# mcu.net
KiCad netlist of a schematic drawn in Altium Designer
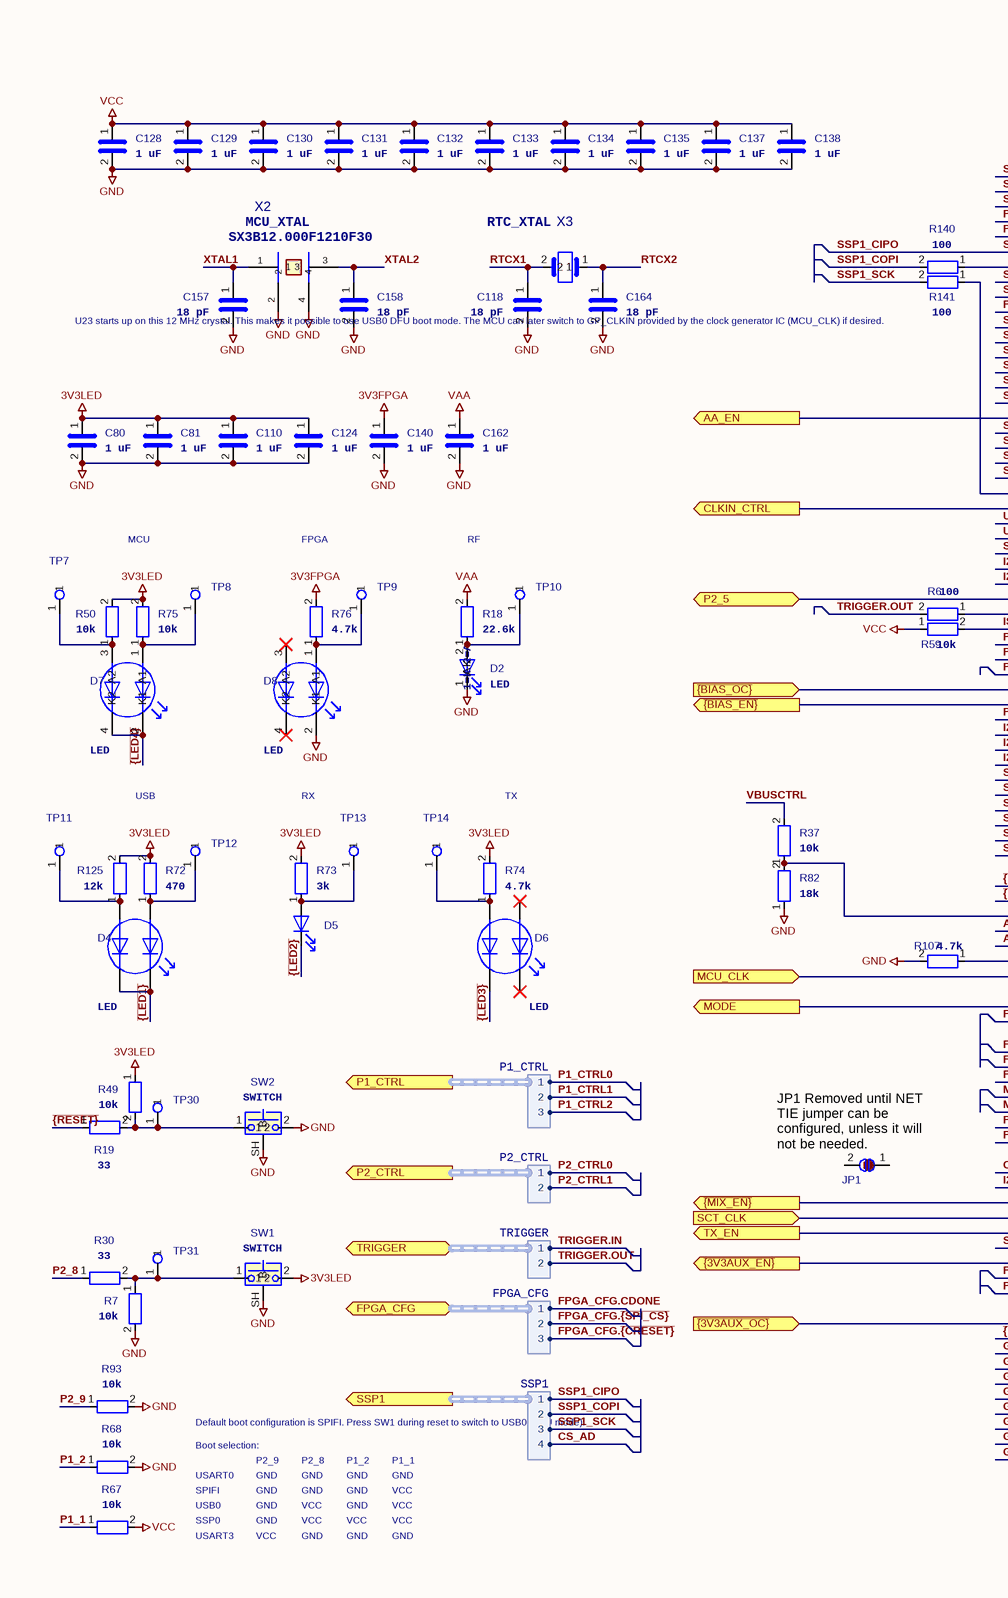
[diagram p0: mcu.SchDoc, left]
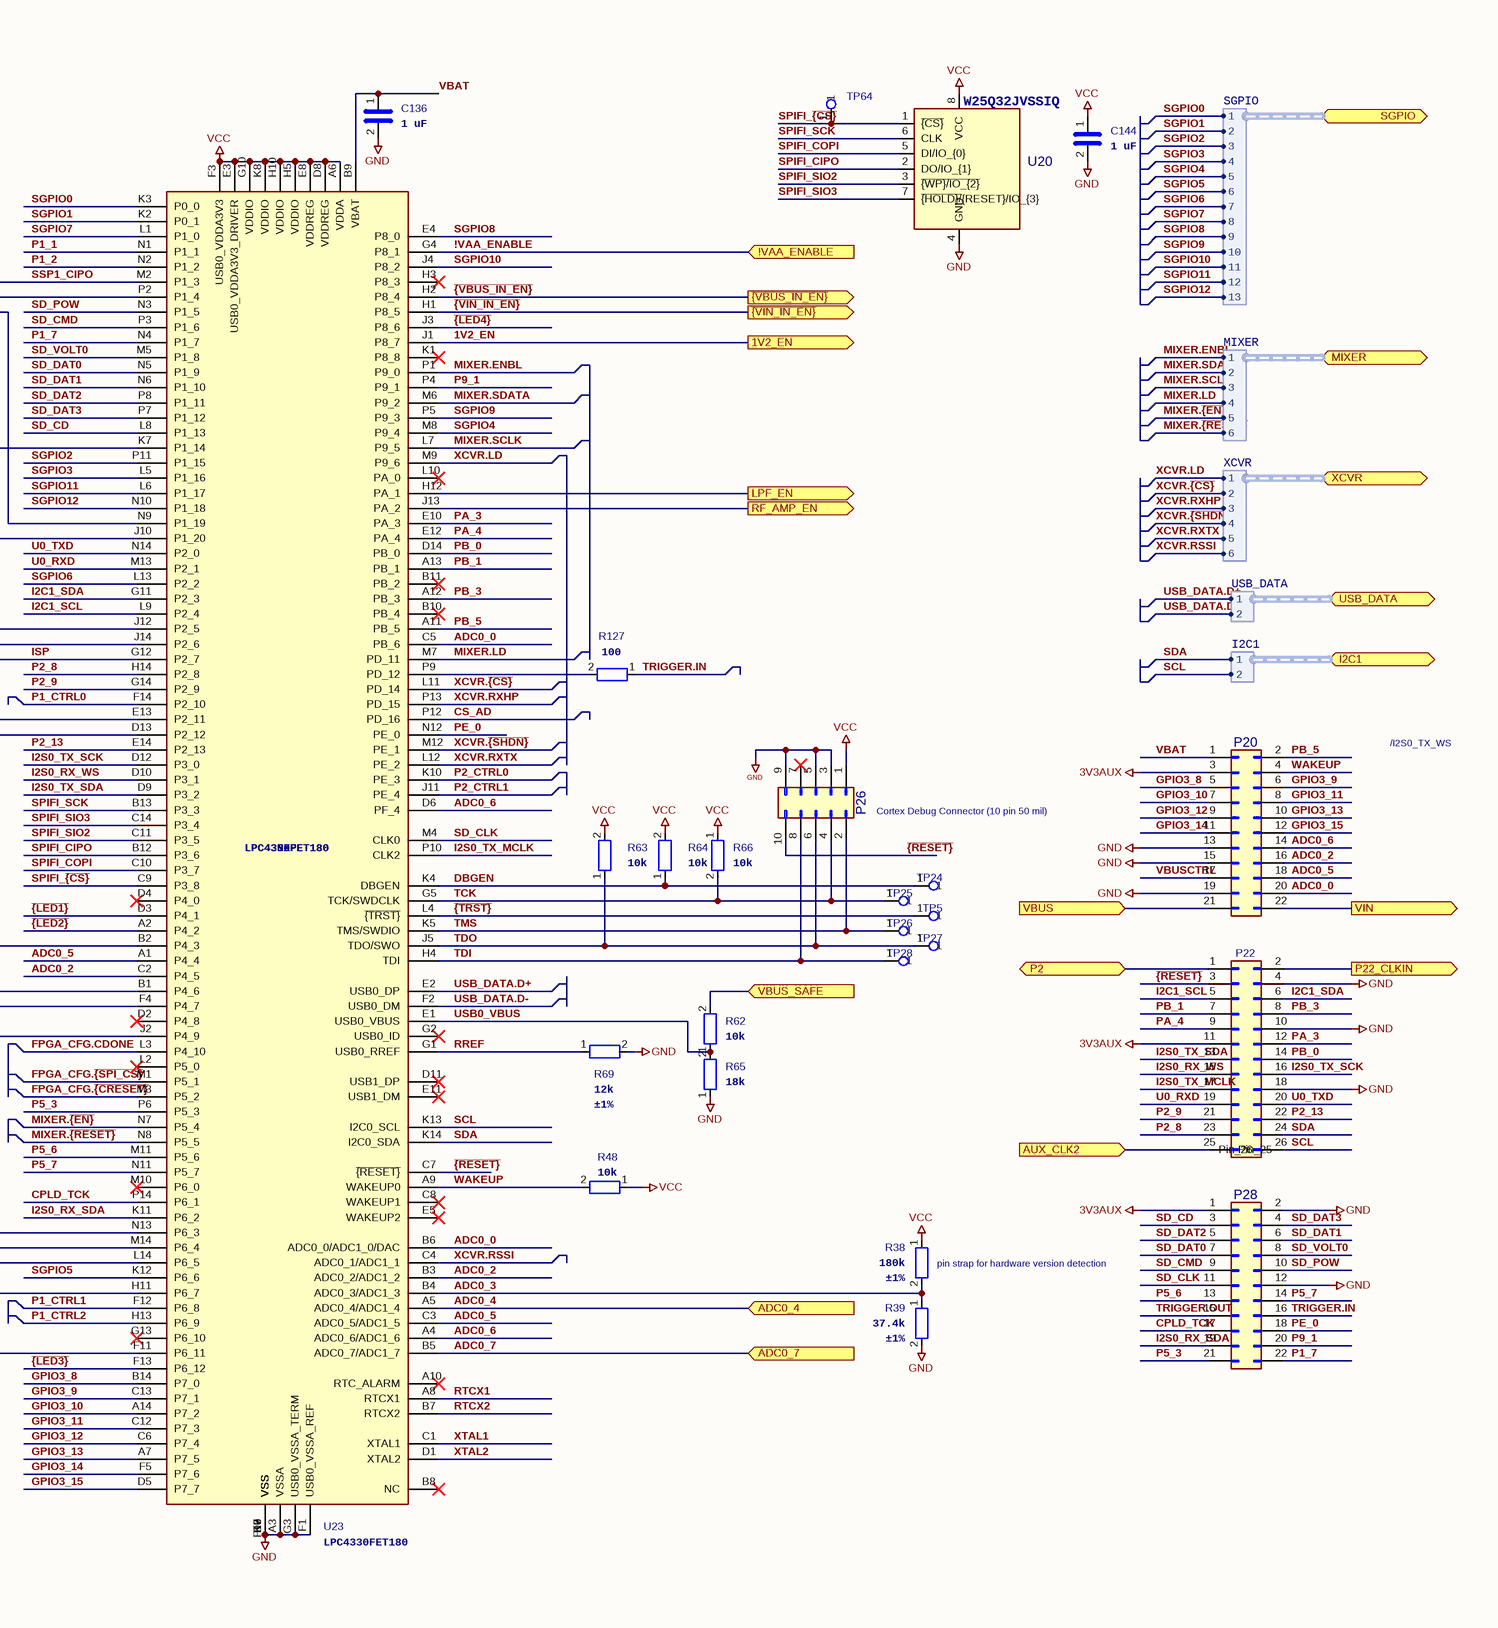
[diagram p1: mcu.SchDoc, right]

(export (version "E")
  (design (tool "Eeschema 10.0.6"))
  (components
    (comp (ref "C80")
      (value "1 uF")
      (footprint "C_0402_1005Metric")
      (fields (field (name "MANUFACTURER") "Samsung") (field (name "PART NUMBER") "CL05A105KA5NQNC"))
      (libsource (lib "Device") (part "C"))
    )
    (comp (ref "C81")
      (value "1 uF")
      (footprint "C_0402_1005Metric")
      (fields (field (name "MANUFACTURER") "Samsung") (field (name "PART NUMBER") "CL05A105KA5NQNC"))
      (libsource (lib "Device") (part "C"))
    )
    (comp (ref "C110")
      (value "1 uF")
      (footprint "C_0402_1005Metric")
      (fields (field (name "MANUFACTURER") "Samsung") (field (name "PART NUMBER") "CL05A105KA5NQNC"))
      (libsource (lib "Device") (part "C"))
    )
    (comp (ref "C118")
      (value "18 pF")
      (footprint "C_0402_1005Metric")
      (fields (field (name "MANUFACTURER") "Samsung") (field (name "PART NUMBER") "CL05C180JB5NNNC"))
      (libsource (lib "Device") (part "C"))
    )
    (comp (ref "C124")
      (value "1 uF")
      (footprint "C_0402_1005Metric")
      (fields (field (name "MANUFACTURER") "Samsung") (field (name "PART NUMBER") "CL05A105KA5NQNC"))
      (libsource (lib "Device") (part "C"))
    )
    (comp (ref "C128")
      (value "1 uF")
      (footprint "C_0402_1005Metric")
      (fields (field (name "MANUFACTURER") "Samsung") (field (name "PART NUMBER") "CL05A105KA5NQNC"))
      (libsource (lib "Device") (part "C"))
    )
    (comp (ref "C129")
      (value "1 uF")
      (footprint "C_0402_1005Metric")
      (fields (field (name "MANUFACTURER") "Samsung") (field (name "PART NUMBER") "CL05A105KA5NQNC"))
      (libsource (lib "Device") (part "C"))
    )
    (comp (ref "C130")
      (value "1 uF")
      (footprint "C_0402_1005Metric")
      (fields (field (name "MANUFACTURER") "Samsung") (field (name "PART NUMBER") "CL05A105KA5NQNC"))
      (libsource (lib "Device") (part "C"))
    )
    (comp (ref "C131")
      (value "1 uF")
      (footprint "C_0402_1005Metric")
      (fields (field (name "MANUFACTURER") "Samsung") (field (name "PART NUMBER") "CL05A105KA5NQNC"))
      (libsource (lib "Device") (part "C"))
    )
    (comp (ref "C132")
      (value "1 uF")
      (footprint "C_0402_1005Metric")
      (fields (field (name "MANUFACTURER") "Samsung") (field (name "PART NUMBER") "CL05A105KA5NQNC"))
      (libsource (lib "Device") (part "C"))
    )
    (comp (ref "C133")
      (value "1 uF")
      (footprint "C_0402_1005Metric")
      (fields (field (name "MANUFACTURER") "Samsung") (field (name "PART NUMBER") "CL05A105KA5NQNC"))
      (libsource (lib "Device") (part "C"))
    )
    (comp (ref "C134")
      (value "1 uF")
      (footprint "C_0402_1005Metric")
      (fields (field (name "MANUFACTURER") "Samsung") (field (name "PART NUMBER") "CL05A105KA5NQNC"))
      (libsource (lib "Device") (part "C"))
    )
    (comp (ref "C135")
      (value "1 uF")
      (footprint "C_0402_1005Metric")
      (fields (field (name "MANUFACTURER") "Samsung") (field (name "PART NUMBER") "CL05A105KA5NQNC"))
      (libsource (lib "Device") (part "C"))
    )
    (comp (ref "C136")
      (value "1 uF")
      (footprint "C_0402_1005Metric")
      (fields (field (name "MANUFACTURER") "Samsung") (field (name "PART NUMBER") "CL05A105KA5NQNC"))
      (libsource (lib "Device") (part "C"))
    )
    (comp (ref "C137")
      (value "1 uF")
      (footprint "C_0402_1005Metric")
      (fields (field (name "MANUFACTURER") "Samsung") (field (name "PART NUMBER") "CL05A105KA5NQNC"))
      (libsource (lib "Device") (part "C"))
    )
    (comp (ref "C138")
      (value "1 uF")
      (footprint "C_0402_1005Metric")
      (fields (field (name "MANUFACTURER") "Samsung") (field (name "PART NUMBER") "CL05A105KA5NQNC"))
      (libsource (lib "Device") (part "C"))
    )
    (comp (ref "C140")
      (value "1 uF")
      (footprint "C_0402_1005Metric")
      (fields (field (name "MANUFACTURER") "Samsung") (field (name "PART NUMBER") "CL05A105KA5NQNC"))
      (libsource (lib "Device") (part "C"))
    )
    (comp (ref "C144")
      (value "1 uF")
      (footprint "C_0402_1005Metric")
      (fields (field (name "MANUFACTURER") "Samsung") (field (name "PART NUMBER") "CL05A105KA5NQNC"))
      (libsource (lib "Device") (part "C"))
    )
    (comp (ref "C157")
      (value "18 pF")
      (footprint "C_0402_1005Metric")
      (fields (field (name "MANUFACTURER") "Samsung") (field (name "PART NUMBER") "CL05C180JB5NNNC"))
      (libsource (lib "Device") (part "C"))
    )
    (comp (ref "C158")
      (value "18 pF")
      (footprint "C_0402_1005Metric")
      (fields (field (name "MANUFACTURER") "Samsung") (field (name "PART NUMBER") "CL05C180JB5NNNC"))
      (libsource (lib "Device") (part "C"))
    )
    (comp (ref "C162")
      (value "1 uF")
      (footprint "C_0402_1005Metric")
      (fields (field (name "MANUFACTURER") "Samsung") (field (name "PART NUMBER") "CL05A105KA5NQNC"))
      (libsource (lib "Device") (part "C"))
    )
    (comp (ref "C164")
      (value "18 pF")
      (footprint "C_0402_1005Metric")
      (fields (field (name "MANUFACTURER") "Samsung") (field (name "PART NUMBER") "CL05C180JB5NNNC"))
      (libsource (lib "Device") (part "C"))
    )
    (comp (ref "D2")
      (value "LED")
      (footprint "LED_Single_Xinglight_XL-3210_Horizontal")
      (fields
        (field (name "MANUFACTURER") "Xinglight")
        (field (name "PART NUMBER") "XL-3210UGC")
        (field (name "SIM.PINS") "1=K 2=A")
      )
      (libsource (lib "") (part "LED_1"))
    )
    (comp (ref "D4")
      (value "LED")
      (footprint "LED_Dual_Xinglight_XL-3210_Horizontal")
      (fields (field (name "MANUFACTURER") "Xinglight") (field (name "PART NUMBER") "XL-3210SURSYGC"))
      (libsource (lib "Device") (part "LED_Dual_AKAK"))
    )
    (comp (ref "D5")
      (value "LED")
      (footprint "LED_Single_Xinglight_XL-3210_Horizontal")
      (fields (field (name "MANUFACTURER") "Xinglight") (field (name "PART NUMBER") "XL-3210UOC"))
      (libsource (lib "Device") (part "LED"))
    )
    (comp (ref "D6")
      (value "LED")
      (footprint "LED_Dual_Xinglight_XL-3210_Horizontal")
      (fields (field (name "MANUFACTURER") "Xinglight") (field (name "PART NUMBER") "XL-3210SURUBC"))
      (libsource (lib "Device") (part "LED_Dual_AKAK"))
    )
    (comp (ref "D7")
      (value "LED")
      (footprint "LED_Dual_Xinglight_XL-3210_Horizontal")
      (fields (field (name "MANUFACTURER") "Xinglight") (field (name "PART NUMBER") "XL-3210SURUBC"))
      (libsource (lib "") (part "LED_Dual_AKAK_1"))
    )
    (comp (ref "D8")
      (value "LED")
      (footprint "LED_Dual_Xinglight_XL-3210_Horizontal")
      (fields (field (name "MANUFACTURER") "Xinglight") (field (name "PART NUMBER") "XL-3210SURUBC"))
      (libsource (lib "") (part "LED_Dual_AKAK_1"))
    )
    (comp (ref "JP1")
      (value "SolderJumper_2_Bridged")
      (footprint "SolderJumper-2_P1.3mm_Bridged_RoundedPad1.0x1.5mm")
      (libsource (lib "Jumper") (part "SolderJumper_2_Bridged"))
    )
    (comp (ref "P20")
      (value "HEADER_2x11")
      (footprint "PinSocket_2x11_P2.54mm_Vertical_Flipped")
      (fields (field (name "MANUFACTURER") "Sullins") (field (name "PART NUMBER") "PPPC112LFBN-RC"))
      (libsource (lib "Connector_Generic") (part "Conn_02x11_Odd_Even"))
    )
    (comp (ref "P22")
      (value "HEADER_2x13")
      (footprint "PinSocket_2x13_P2.54mm_Vertical_Flipped")
      (fields (field (name "MANUFACTURER") "Sullins") (field (name "PART NUMBER") "PPPC132LFBN-RC"))
      (libsource (lib "Connector_Generic") (part "Conn_02x13_Odd_Even"))
    )
    (comp (ref "P26")
      (value "LPC_JTAG")
      (footprint "PinHeader_2x05_P1.27mm_Vertical")
      (fields (field (name "MANUFACTURER") "Sullins") (field (name "PART NUMBER") "GRPB052VWVN-RC"))
      (libsource (lib "Connector_Generic") (part "Conn_02x05_Odd_Even"))
    )
    (comp (ref "P28")
      (value "HEADER_2x11")
      (footprint "PinSocket_2x11_P2.54mm_Vertical_Flipped")
      (fields (field (name "MANUFACTURER") "Sullins") (field (name "PART NUMBER") "PPPC112LFBN-RC"))
      (libsource (lib "Connector_Generic") (part "Conn_02x11_Odd_Even"))
    )
    (comp (ref "R6")
      (value "100")
      (footprint "R_0201_0603Metric")
      (fields (field (name "MANUFACTURER") "Yageo") (field (name "PART NUMBER") "RC0201JR-07100RL"))
      (libsource (lib "") (part "R_2"))
    )
    (comp (ref "R7")
      (value "10k")
      (footprint "R_0402_1005Metric")
      (fields (field (name "MANUFACTURER") "Yageo") (field (name "PART NUMBER") "RC0402JR-0710KL"))
      (libsource (lib "") (part "R_3"))
    )
    (comp (ref "R18")
      (value "22.6k")
      (footprint "R_0201_0603Metric")
      (fields (field (name "MANUFACTURER") "Yageo") (field (name "PART NUMBER") "RC0201FR-0722K6L"))
      (libsource (lib "") (part "R_1"))
    )
    (comp (ref "R19")
      (value "33")
      (footprint "R_0201_0603Metric")
      (fields (field (name "MANUFACTURER") "Yageo") (field (name "PART NUMBER") "RC0201JR-0733RL"))
      (libsource (lib "") (part "R_1"))
    )
    (comp (ref "R30")
      (value "33")
      (footprint "R_0201_0603Metric")
      (fields (field (name "MANUFACTURER") "Yageo") (field (name "PART NUMBER") "RC0201JR-0733RL"))
      (libsource (lib "Device") (part "R"))
    )
    (comp (ref "R37")
      (value "10k")
      (footprint "R_0402_1005Metric")
      (fields (field (name "MANUFACTURER") "Yageo") (field (name "PART NUMBER") "RC0402JR-0710KL"))
      (libsource (lib "") (part "R_1"))
    )
    (comp (ref "R38")
      (value "180k")
      (footprint "R_0402_1005Metric")
      (fields
        (field (name "MANUFACTURER") "Yageo")
        (field (name "PART NUMBER") "RC0402FR-07180KL")
        (field (name "TOLERANCE") "±1%")
      )
      (libsource (lib "") (part "R_2"))
    )
    (comp (ref "R39")
      (value "37.4k")
      (footprint "R_0402_1005Metric")
      (fields
        (field (name "MANUFACTURER") "Yageo")
        (field (name "PART NUMBER") "RC0402FR-0737K4L")
        (field (name "TOLERANCE") "±1%")
      )
      (libsource (lib "") (part "R_2"))
    )
    (comp (ref "R48")
      (value "10k")
      (footprint "R_0402_1005Metric")
      (fields (field (name "MANUFACTURER") "Yageo") (field (name "PART NUMBER") "RC0402JR-0710KL"))
      (libsource (lib "") (part "R_3"))
    )
    (comp (ref "R49")
      (value "10k")
      (footprint "R_0402_1005Metric")
      (fields (field (name "MANUFACTURER") "Yageo") (field (name "PART NUMBER") "RC0402JR-0710KL"))
      (libsource (lib "") (part "R_2"))
    )
    (comp (ref "R50")
      (value "10k")
      (footprint "R_0402_1005Metric")
      (fields (field (name "MANUFACTURER") "Yageo") (field (name "PART NUMBER") "RC0402JR-0710KL"))
      (libsource (lib "") (part "R_1"))
    )
    (comp (ref "R59")
      (value "10k")
      (footprint "R_0402_1005Metric")
      (fields (field (name "MANUFACTURER") "Yageo") (field (name "PART NUMBER") "RC0402JR-0710KL"))
      (libsource (lib "Device") (part "R"))
    )
    (comp (ref "R62")
      (value "10k")
      (footprint "R_0402_1005Metric")
      (fields (field (name "MANUFACTURER") "Yageo") (field (name "PART NUMBER") "RC0402JR-0710KL"))
      (libsource (lib "") (part "R_1"))
    )
    (comp (ref "R63")
      (value "10k")
      (footprint "R_0402_1005Metric")
      (fields (field (name "MANUFACTURER") "Yageo") (field (name "PART NUMBER") "RC0402JR-0710KL"))
      (libsource (lib "") (part "R_1"))
    )
    (comp (ref "R64")
      (value "10k")
      (footprint "R_0402_1005Metric")
      (fields (field (name "MANUFACTURER") "Yageo") (field (name "PART NUMBER") "RC0402JR-0710KL"))
      (libsource (lib "") (part "R_1"))
    )
    (comp (ref "R65")
      (value "18k")
      (footprint "R_0402_1005Metric")
      (fields (field (name "MANUFACTURER") "Yageo") (field (name "PART NUMBER") "RC0402JR-0718KL"))
      (libsource (lib "") (part "R_1"))
    )
    (comp (ref "R66")
      (value "10k")
      (footprint "R_0402_1005Metric")
      (fields (field (name "MANUFACTURER") "Yageo") (field (name "PART NUMBER") "RC0402JR-0710KL"))
      (libsource (lib "") (part "R_2"))
    )
    (comp (ref "R67")
      (value "10k")
      (footprint "R_0402_1005Metric")
      (fields (field (name "MANUFACTURER") "Yageo") (field (name "PART NUMBER") "RC0402JR-0710KL"))
      (libsource (lib "Device") (part "R"))
    )
    (comp (ref "R68")
      (value "10k")
      (footprint "R_0402_1005Metric")
      (fields (field (name "MANUFACTURER") "Yageo") (field (name "PART NUMBER") "RC0402JR-0710KL"))
      (libsource (lib "") (part "R_1"))
    )
    (comp (ref "R69")
      (value "12k")
      (footprint "R_0201_0603Metric")
      (fields
        (field (name "MANUFACTURER") "Yageo")
        (field (name "PART NUMBER") "RC0201FR-0712KL")
        (field (name "TOLERANCE") "±1%")
      )
      (libsource (lib "") (part "R_1"))
    )
    (comp (ref "R72")
      (value "470")
      (footprint "R_0201_0603Metric")
      (fields (field (name "MANUFACTURER") "Yageo") (field (name "PART NUMBER") "RC0201JR-07470RL"))
      (libsource (lib "") (part "R_1"))
    )
    (comp (ref "R73")
      (value "3k")
      (footprint "R_0402_1005Metric")
      (fields (field (name "MANUFACTURER") "Yageo") (field (name "PART NUMBER") "RC0402JR-073KL"))
      (libsource (lib "") (part "R_1"))
    )
    (comp (ref "R74")
      (value "4.7k")
      (footprint "R_0201_0603Metric")
      (fields (field (name "MANUFACTURER") "Yageo") (field (name "PART NUMBER") "RC0201FR-074K7L"))
      (libsource (lib "") (part "R_1"))
    )
    (comp (ref "R75")
      (value "10k")
      (footprint "R_0402_1005Metric")
      (fields (field (name "MANUFACTURER") "Yageo") (field (name "PART NUMBER") "RC0402JR-0710KL"))
      (libsource (lib "") (part "R_1"))
    )
    (comp (ref "R76")
      (value "4.7k")
      (footprint "R_0201_0603Metric")
      (fields (field (name "MANUFACTURER") "Yageo") (field (name "PART NUMBER") "RC0201FR-074K7L"))
      (libsource (lib "") (part "R_1"))
    )
    (comp (ref "R82")
      (value "18k")
      (footprint "R_0402_1005Metric")
      (fields (field (name "MANUFACTURER") "Yageo") (field (name "PART NUMBER") "RC0402JR-0718KL"))
      (libsource (lib "") (part "R_1"))
    )
    (comp (ref "R93")
      (value "10k")
      (footprint "R_0402_1005Metric")
      (fields (field (name "MANUFACTURER") "Yageo") (field (name "PART NUMBER") "RC0402JR-0710KL"))
      (libsource (lib "") (part "R_1"))
    )
    (comp (ref "R107")
      (value "4.7k")
      (footprint "R_0201_0603Metric")
      (fields (field (name "MANUFACTURER") "Yageo") (field (name "PART NUMBER") "RC0201FR-074K7L"))
      (libsource (lib "") (part "R_2"))
    )
    (comp (ref "R125")
      (value "12k")
      (footprint "R_0201_0603Metric")
      (fields (field (name "MANUFACTURER") "Yageo") (field (name "PART NUMBER") "RC0201FR-0712KL"))
      (libsource (lib "") (part "R_1"))
    )
    (comp (ref "R127")
      (value "100")
      (footprint "R_0201_0603Metric")
      (fields (field (name "MANUFACTURER") "Yageo") (field (name "PART NUMBER") "RC0201JR-07100RL"))
      (libsource (lib "") (part "R_2"))
    )
    (comp (ref "R140")
      (value "100")
      (footprint "R_0201_0603Metric")
      (fields (field (name "MANUFACTURER") "Yageo") (field (name "PART NUMBER") "RC0201JR-07100RL"))
      (libsource (lib "") (part "R_2"))
    )
    (comp (ref "R141")
      (value "100")
      (footprint "R_0201_0603Metric")
      (fields (field (name "MANUFACTURER") "Yageo") (field (name "PART NUMBER") "RC0201JR-07100RL"))
      (libsource (lib "") (part "R_2"))
    )
    (comp (ref "SW1")
      (value "SWITCH")
      (footprint "SW_Tactile_SPST_Angled_PTS645Vx58-2LFS")
      (fields (field (name "MANUFACTURER") "TE Connectivity") (field (name "PART NUMBER") "FSMRA3JH"))
      (libsource (lib "Switch") (part "SW_Push_Shielded"))
    )
    (comp (ref "SW2")
      (value "SWITCH")
      (footprint "SW_Tactile_SPST_Angled_PTS645Vx58-2LFS")
      (fields (field (name "MANUFACTURER") "TE Connectivity") (field (name "PART NUMBER") "FSMRA3JH"))
      (libsource (lib "Switch") (part "SW_Push_Shielded"))
    )
    (comp (ref "TP5")
      (value "TestPoint")
      (footprint "TestPoint_Pad_D1.0mm")
      (libsource (lib "Connector") (part "TestPoint"))
    )
    (comp (ref "TP7")
      (value "TestPoint")
      (footprint "TestPoint_Pad_D1.0mm")
      (libsource (lib "Connector") (part "TestPoint"))
    )
    (comp (ref "TP8")
      (value "TestPoint")
      (footprint "TestPoint_Pad_D1.0mm")
      (libsource (lib "Connector") (part "TestPoint"))
    )
    (comp (ref "TP9")
      (value "TestPoint")
      (footprint "TestPoint_Pad_D1.0mm")
      (libsource (lib "Connector") (part "TestPoint"))
    )
    (comp (ref "TP10")
      (value "TestPoint")
      (footprint "TestPoint_Pad_D1.0mm")
      (libsource (lib "Connector") (part "TestPoint"))
    )
    (comp (ref "TP11")
      (value "TestPoint")
      (footprint "TestPoint_Pad_D1.0mm")
      (libsource (lib "Connector") (part "TestPoint"))
    )
    (comp (ref "TP12")
      (value "TestPoint")
      (footprint "TestPoint_Pad_D1.0mm")
      (libsource (lib "Connector") (part "TestPoint"))
    )
    (comp (ref "TP13")
      (value "TestPoint")
      (footprint "TestPoint_Pad_D1.0mm")
      (libsource (lib "Connector") (part "TestPoint"))
    )
    (comp (ref "TP14")
      (value "TestPoint")
      (footprint "TestPoint_Pad_D1.0mm")
      (libsource (lib "Connector") (part "TestPoint"))
    )
    (comp (ref "TP24")
      (value "TestPoint")
      (footprint "TestPoint_Pad_D1.0mm")
      (libsource (lib "Connector") (part "TestPoint"))
    )
    (comp (ref "TP25")
      (value "TestPoint")
      (footprint "TestPoint_Pad_D1.0mm")
      (libsource (lib "Connector") (part "TestPoint"))
    )
    (comp (ref "TP26")
      (value "TestPoint")
      (footprint "TestPoint_Pad_D1.0mm")
      (libsource (lib "Connector") (part "TestPoint"))
    )
    (comp (ref "TP27")
      (value "TestPoint")
      (footprint "TestPoint_Pad_D1.0mm")
      (libsource (lib "Connector") (part "TestPoint"))
    )
    (comp (ref "TP28")
      (value "TestPoint")
      (footprint "TestPoint_Pad_D1.0mm")
      (libsource (lib "Connector") (part "TestPoint"))
    )
    (comp (ref "TP30")
      (value "TestPoint")
      (footprint "TestPoint_Pad_D1.0mm")
      (libsource (lib "Connector") (part "TestPoint"))
    )
    (comp (ref "TP31")
      (value "TestPoint")
      (footprint "TestPoint_Pad_D1.0mm")
      (libsource (lib "Connector") (part "TestPoint"))
    )
    (comp (ref "TP64")
      (value "TestPoint")
      (footprint "TestPoint_Pad_D1.0mm")
      (libsource (lib "Connector") (part "TestPoint"))
    )
    (comp (ref "U20")
      (value "W25Q32")
      (footprint "SOIC-8_5.3x5.3mm_P1.27mm")
      (fields (field (name "MANUFACTURER") "Winbond") (field (name "PART NUMBER") "W25Q32JVSSIQ"))
      (libsource (lib "Memory_Flash") (part "W25Q32JVSS"))
    )
    (comp (ref "U23")
      (value "LPC4330FET180")
      (footprint "TFBGA-180_12x12mm_Layout14x14_P0.8mm")
      (fields
        (field (name "MANUFACTURER") "NXP")
        (field (name "PART NUMBER") "LPC4330FET180")
        (field (name "SUBSTITUTION") "LPC4350FET180")
      )
      (libsource (lib "praline") (part "LPC43xxFET180"))
    )
    (comp (ref "X2")
      (value "MCU_XTAL")
      (footprint "Crystal_SMD_3225-4Pin_3.2x2.5mm")
      (fields
        (field (name "MANUFACTURER") "Shenzhen SCTF Electronics")
        (field (name "PART NUMBER") "SX3B12.000F1210F30")
      )
      (libsource (lib "hackrf") (part "GSG-XTAL4PIN"))
    )
    (comp (ref "X3")
      (value "RTC_XTAL")
      (footprint "Crystal_SMD_3215-2Pin_3.2x1.5mm")
      (fields (field (name "MANUFACTURER") "YXC") (field (name "PART NUMBER") "XKXGI-SUA-32.768K"))
      (libsource (lib "Device") (part "Crystal"))
    )
  )
  (nets
    (net (code "11") (name "/!VAA_ENABLE") (class "Default")
      (node (ref "U23") (pin "G4") (pinfunction "P8_1_G4") (pintype "passive"))
    )
    (net (code "12") (name "/1V2_EN") (class "Default")
      (node (ref "U23") (pin "J1") (pinfunction "P8_7_J1") (pintype "passive"))
    )
    (net (code "13") (name "/AA_EN") (class "Default")
      (node (ref "U23") (pin "K7") (pinfunction "P1_14_K7") (pintype "passive"))
    )
    (net (code "14") (name "/ADC0_0") (class "Default")
      (node (ref "P20") (pin "20") (pinfunction "Pin_20_20") (pintype "passive"))
      (node (ref "U23") (pin "B6") (pinfunction "ADC0_0/ADC1_0/DAC_B6") (pintype "passive"))
      (node (ref "U23") (pin "C5") (pinfunction "PB_6_C5") (pintype "passive"))
    )
    (net (code "15") (name "/ADC0_2") (class "Default")
      (node (ref "P20") (pin "16") (pinfunction "Pin_16_16") (pintype "passive"))
      (node (ref "U23") (pin "B3") (pinfunction "ADC0_2/ADC1_2_B3") (pintype "passive"))
      (node (ref "U23") (pin "C2") (pinfunction "P4_5_C2") (pintype "passive"))
    )
    (net (code "16") (name "/ADC0_3") (class "Default")
      (node (ref "R38") (pin "2") (pinfunction "2_2") (pintype "passive"))
      (node (ref "R39") (pin "1") (pinfunction "1_1") (pintype "passive"))
      (node (ref "U23") (pin "B4") (pinfunction "ADC0_3/ADC1_3_B4") (pintype "passive"))
    )
    (net (code "17") (name "/ADC0_4") (class "Default")
      (node (ref "U23") (pin "A5") (pinfunction "ADC0_4/ADC1_4_A5") (pintype "passive"))
    )
    (net (code "18") (name "/ADC0_5") (class "Default")
      (node (ref "P20") (pin "18") (pinfunction "Pin_18_18") (pintype "passive"))
      (node (ref "U23") (pin "A1") (pinfunction "P4_4_A1") (pintype "passive"))
      (node (ref "U23") (pin "C3") (pinfunction "ADC0_5/ADC1_5_C3") (pintype "passive"))
    )
    (net (code "19") (name "/ADC0_6") (class "Default")
      (node (ref "P20") (pin "14") (pinfunction "Pin_14_14") (pintype "passive"))
      (node (ref "U23") (pin "A4") (pinfunction "ADC0_6/ADC1_6_A4") (pintype "passive"))
      (node (ref "U23") (pin "D6") (pinfunction "PF_4_D6") (pintype "passive"))
    )
    (net (code "20") (name "/ADC0_7") (class "Default")
      (node (ref "U23") (pin "B5") (pinfunction "ADC0_7/ADC1_7_B5") (pintype "passive"))
    )
    (net (code "21") (name "/AUX_CLK2") (class "Default")
      (node (ref "P22") (pin "25") (pinfunction "Pin_25_25") (pintype "passive"))
    )
    (net (code "22") (name "/CLKIN_CTRL") (class "Default")
      (node (ref "U23") (pin "J10") (pinfunction "P1_20_J10") (pintype "passive"))
    )
    (net (code "23") (name "/CPLD_TCK") (class "Default")
      (node (ref "P28") (pin "17") (pinfunction "Pin_17_17") (pintype "passive"))
      (node (ref "U23") (pin "P14") (pinfunction "P6_1_P14") (pintype "passive"))
    )
    (net (code "24") (name "/CS_AD") (class "Default")
      (node (ref "U23") (pin "P12") (pinfunction "PD_16_P12") (pintype "passive"))
    )
    (net (code "25") (name "/DBGEN") (class "Default")
      (node (ref "R64") (pin "1") (pinfunction "1_1") (pintype "passive"))
      (node (ref "TP24") (pin "1") (pinfunction "1_1") (pintype "passive"))
      (node (ref "U23") (pin "K4") (pinfunction "DBGEN_K4") (pintype "passive"))
    )
    (net (code "26") (name "/FPGA_CFG.CDONE") (class "Default")
      (node (ref "U23") (pin "L3") (pinfunction "P4_10_L3") (pintype "passive"))
    )
    (net (code "27") (name "/FPGA_CFG.~{{CRESET}}") (class "Default")
      (node (ref "U23") (pin "M3") (pinfunction "P5_2_M3") (pintype "passive"))
    )
    (net (code "28") (name "/FPGA_CFG.~{{SPI_CS}}") (class "Default")
      (node (ref "U23") (pin "M1") (pinfunction "P5_1_M1") (pintype "passive"))
    )
    (net (code "29") (name "/GPIO3_8") (class "Default")
      (node (ref "P20") (pin "5") (pinfunction "Pin_5_5") (pintype "passive"))
      (node (ref "U23") (pin "B14") (pinfunction "P7_0_B14") (pintype "passive"))
    )
    (net (code "30") (name "/GPIO3_9") (class "Default")
      (node (ref "P20") (pin "6") (pinfunction "Pin_6_6") (pintype "passive"))
      (node (ref "U23") (pin "C13") (pinfunction "P7_1_C13") (pintype "passive"))
    )
    (net (code "31") (name "/GPIO3_10") (class "Default")
      (node (ref "P20") (pin "7") (pinfunction "Pin_7_7") (pintype "passive"))
      (node (ref "U23") (pin "A14") (pinfunction "P7_2_A14") (pintype "passive"))
    )
    (net (code "32") (name "/GPIO3_11") (class "Default")
      (node (ref "P20") (pin "8") (pinfunction "Pin_8_8") (pintype "passive"))
      (node (ref "U23") (pin "C12") (pinfunction "P7_3_C12") (pintype "passive"))
    )
    (net (code "33") (name "/GPIO3_12") (class "Default")
      (node (ref "P20") (pin "9") (pinfunction "Pin_9_9") (pintype "passive"))
      (node (ref "U23") (pin "C6") (pinfunction "P7_4_C6") (pintype "passive"))
    )
    (net (code "34") (name "/GPIO3_13") (class "Default")
      (node (ref "P20") (pin "10") (pinfunction "Pin_10_10") (pintype "passive"))
      (node (ref "U23") (pin "A7") (pinfunction "P7_5_A7") (pintype "passive"))
    )
    (net (code "35") (name "/GPIO3_14") (class "Default")
      (node (ref "P20") (pin "11") (pinfunction "Pin_11_11") (pintype "passive"))
      (node (ref "U23") (pin "F5") (pinfunction "P7_6_F5") (pintype "passive"))
    )
    (net (code "36") (name "/GPIO3_15") (class "Default")
      (node (ref "P20") (pin "12") (pinfunction "Pin_12_12") (pintype "passive"))
      (node (ref "U23") (pin "D5") (pinfunction "P7_7_D5") (pintype "passive"))
    )
    (net (code "37") (name "/I2C1_SCL") (class "Default")
      (node (ref "P22") (pin "5") (pinfunction "Pin_5_5") (pintype "passive"))
      (node (ref "U23") (pin "L9") (pinfunction "P2_4_L9") (pintype "passive"))
    )
    (net (code "38") (name "/I2C1_SDA") (class "Default")
      (node (ref "P22") (pin "6") (pinfunction "Pin_6_6") (pintype "passive"))
      (node (ref "U23") (pin "G11") (pinfunction "P2_3_G11") (pintype "passive"))
    )
    (net (code "39") (name "/I2S0_RX_SDA") (class "Default")
      (node (ref "P28") (pin "19") (pinfunction "Pin_19_19") (pintype "passive"))
      (node (ref "U23") (pin "K11") (pinfunction "P6_2_K11") (pintype "passive"))
    )
    (net (code "40") (name "/I2S0_RX_WS") (class "Default")
      (node (ref "P22") (pin "15") (pinfunction "Pin_15_15") (pintype "passive"))
      (node (ref "U23") (pin "D10") (pinfunction "P3_1_D10") (pintype "passive"))
    )
    (net (code "41") (name "/I2S0_TX_MCLK") (class "Default")
      (node (ref "P22") (pin "17") (pinfunction "Pin_17_17") (pintype "passive"))
      (node (ref "U23") (pin "P10") (pinfunction "CLK2_P10") (pintype "passive"))
    )
    (net (code "42") (name "/I2S0_TX_SCK") (class "Default")
      (node (ref "P22") (pin "16") (pinfunction "Pin_16_16") (pintype "passive"))
      (node (ref "U23") (pin "D12") (pinfunction "P3_0_D12") (pintype "passive"))
    )
    (net (code "43") (name "/I2S0_TX_SDA") (class "Default")
      (node (ref "P22") (pin "13") (pinfunction "Pin_13_13") (pintype "passive"))
      (node (ref "U23") (pin "D9") (pinfunction "P3_2_D9") (pintype "passive"))
    )
    (net (code "44") (name "/ISP") (class "Default")
      (node (ref "R59") (pin "2") (pinfunction "2_2") (pintype "passive"))
      (node (ref "U23") (pin "G12") (pinfunction "P2_7_G12") (pintype "passive"))
    )
    (net (code "45") (name "/LPF_EN") (class "Default")
      (node (ref "U23") (pin "H12") (pinfunction "PA_1_H12") (pintype "passive"))
    )
    (net (code "46") (name "/MCU_CLK") (class "Default")
      (node (ref "U23") (pin "F4") (pinfunction "P4_7_F4") (pintype "passive"))
    )
    (net (code "47") (name "/MIXER.ENBL") (class "Default")
      (node (ref "U23") (pin "P1") (pinfunction "P9_0_P1") (pintype "passive"))
    )
    (net (code "48") (name "/MIXER.LD") (class "Default")
      (node (ref "U23") (pin "M7") (pinfunction "PD_11_M7") (pintype "passive"))
    )
    (net (code "49") (name "/MIXER.SCLK") (class "Default")
      (node (ref "U23") (pin "L7") (pinfunction "P9_5_L7") (pintype "passive"))
    )
    (net (code "50") (name "/MIXER.SDATA") (class "Default")
      (node (ref "U23") (pin "M6") (pinfunction "P9_2_M6") (pintype "passive"))
    )
    (net (code "51") (name "/MIXER.~{{EN}}") (class "Default")
      (node (ref "U23") (pin "N7") (pinfunction "P5_4_N7") (pintype "passive"))
    )
    (net (code "52") (name "/MIXER.~{{RESET}}") (class "Default")
      (node (ref "U23") (pin "N8") (pinfunction "P5_5_N8") (pintype "passive"))
    )
    (net (code "53") (name "/MODE") (class "Default")
      (node (ref "U23") (pin "J2") (pinfunction "P4_9_J2") (pintype "passive"))
    )
    (net (code "54") (name "/P1_1") (class "Default")
      (node (ref "R67") (pin "1") (pinfunction "1_1") (pintype "passive"))
      (node (ref "U23") (pin "N1") (pinfunction "P1_1_N1") (pintype "passive"))
    )
    (net (code "55") (name "/P1_2") (class "Default")
      (node (ref "R68") (pin "1") (pinfunction "1_1") (pintype "passive"))
      (node (ref "U23") (pin "N2") (pinfunction "P1_2_N2") (pintype "passive"))
    )
    (net (code "56") (name "/P1_7") (class "Default")
      (node (ref "P28") (pin "22") (pinfunction "Pin_22_22") (pintype "passive"))
      (node (ref "U23") (pin "N4") (pinfunction "P1_7_N4") (pintype "passive"))
    )
    (net (code "57") (name "/P1_CTRL0") (class "Default")
      (node (ref "U23") (pin "F14") (pinfunction "P2_10_F14") (pintype "passive"))
    )
    (net (code "58") (name "/P1_CTRL1") (class "Default")
      (node (ref "U23") (pin "F12") (pinfunction "P6_8_F12") (pintype "passive"))
    )
    (net (code "59") (name "/P1_CTRL2") (class "Default")
      (node (ref "U23") (pin "H13") (pinfunction "P6_9_H13") (pintype "passive"))
    )
    (net (code "60") (name "/P2") (class "Default")
      (node (ref "P22") (pin "1") (pinfunction "Pin_1_1") (pintype "passive"))
    )
    (net (code "61") (name "/P2_5") (class "Default")
      (node (ref "U23") (pin "J12") (pinfunction "P2_5_J12") (pintype "passive"))
    )
    (net (code "62") (name "/P2_8") (class "Default")
      (node (ref "P22") (pin "23") (pinfunction "Pin_23_23") (pintype "passive"))
      (node (ref "R30") (pin "1") (pinfunction "1_1") (pintype "passive"))
      (node (ref "U23") (pin "H14") (pinfunction "P2_8_H14") (pintype "passive"))
    )
    (net (code "63") (name "/P2_9") (class "Default")
      (node (ref "P22") (pin "21") (pinfunction "Pin_21_21") (pintype "passive"))
      (node (ref "R93") (pin "1") (pinfunction "1_1") (pintype "passive"))
      (node (ref "U23") (pin "G14") (pinfunction "P2_9_G14") (pintype "passive"))
    )
    (net (code "64") (name "/P2_13") (class "Default")
      (node (ref "P22") (pin "22") (pinfunction "Pin_22_22") (pintype "passive"))
      (node (ref "U23") (pin "E14") (pinfunction "P2_13_E14") (pintype "passive"))
    )
    (net (code "65") (name "/P2_CTRL0") (class "Default")
      (node (ref "U23") (pin "K10") (pinfunction "PE_3_K10") (pintype "passive"))
    )
    (net (code "66") (name "/P2_CTRL1") (class "Default")
      (node (ref "U23") (pin "J11") (pinfunction "PE_4_J11") (pintype "passive"))
    )
    (net (code "67") (name "/P5_3") (class "Default")
      (node (ref "P28") (pin "21") (pinfunction "Pin_21_21") (pintype "passive"))
      (node (ref "U23") (pin "P6") (pinfunction "P5_3_P6") (pintype "passive"))
    )
    (net (code "68") (name "/P5_6") (class "Default")
      (node (ref "P28") (pin "13") (pinfunction "Pin_13_13") (pintype "passive"))
      (node (ref "U23") (pin "M11") (pinfunction "P5_6_M11") (pintype "passive"))
    )
    (net (code "69") (name "/P5_7") (class "Default")
      (node (ref "P28") (pin "14") (pinfunction "Pin_14_14") (pintype "passive"))
      (node (ref "U23") (pin "N11") (pinfunction "P5_7_N11") (pintype "passive"))
    )
    (net (code "70") (name "/P9_1") (class "Default")
      (node (ref "P28") (pin "20") (pinfunction "Pin_20_20") (pintype "passive"))
      (node (ref "U23") (pin "P4") (pinfunction "P9_1_P4") (pintype "passive"))
    )
    (net (code "71") (name "/P22_CLKIN") (class "Default")
      (node (ref "P22") (pin "2") (pinfunction "Pin_2_2") (pintype "passive"))
    )
    (net (code "72") (name "/PA_3") (class "Default")
      (node (ref "P22") (pin "12") (pinfunction "Pin_12_12") (pintype "passive"))
      (node (ref "U23") (pin "E10") (pinfunction "PA_3_E10") (pintype "passive"))
    )
    (net (code "73") (name "/PA_4") (class "Default")
      (node (ref "P22") (pin "9") (pinfunction "Pin_9_9") (pintype "passive"))
      (node (ref "U23") (pin "E12") (pinfunction "PA_4_E12") (pintype "passive"))
    )
    (net (code "74") (name "/PB_0") (class "Default")
      (node (ref "P22") (pin "14") (pinfunction "Pin_14_14") (pintype "passive"))
      (node (ref "U23") (pin "D14") (pinfunction "PB_0_D14") (pintype "passive"))
    )
    (net (code "75") (name "/PB_1") (class "Default")
      (node (ref "P22") (pin "7") (pinfunction "Pin_7_7") (pintype "passive"))
      (node (ref "U23") (pin "A13") (pinfunction "PB_1_A13") (pintype "passive"))
    )
    (net (code "76") (name "/PB_3") (class "Default")
      (node (ref "P22") (pin "8") (pinfunction "Pin_8_8") (pintype "passive"))
      (node (ref "U23") (pin "A12") (pinfunction "PB_3_A12") (pintype "passive"))
    )
    (net (code "77") (name "/PB_5") (class "Default")
      (node (ref "P20") (pin "2") (pinfunction "Pin_2_2") (pintype "passive"))
      (node (ref "U23") (pin "A11") (pinfunction "PB_5_A11") (pintype "passive"))
    )
    (net (code "78") (name "/PE_0") (class "Default")
      (node (ref "P28") (pin "18") (pinfunction "Pin_18_18") (pintype "passive"))
      (node (ref "U23") (pin "N12") (pinfunction "PE_0_N12") (pintype "passive"))
    )
    (net (code "79") (name "/RF_AMP_EN") (class "Default")
      (node (ref "U23") (pin "J13") (pinfunction "PA_2_J13") (pintype "passive"))
    )
    (net (code "80") (name "/RREF") (class "Default")
      (node (ref "R69") (pin "1") (pinfunction "1_1") (pintype "passive"))
      (node (ref "U23") (pin "G1") (pinfunction "USB0_RREF_G1") (pintype "passive"))
    )
    (net (code "81") (name "/RTCX1") (class "Default")
      (node (ref "C118") (pin "1") (pinfunction "1_1") (pintype "passive"))
      (node (ref "U23") (pin "A8") (pinfunction "RTCX1_A8") (pintype "passive"))
      (node (ref "X3") (pin "2") (pinfunction "2_2") (pintype "passive"))
    )
    (net (code "82") (name "/RTCX2") (class "Default")
      (node (ref "C164") (pin "1") (pinfunction "1_1") (pintype "passive"))
      (node (ref "U23") (pin "B7") (pinfunction "RTCX2_B7") (pintype "passive"))
      (node (ref "X3") (pin "1") (pinfunction "1_1") (pintype "passive"))
    )
    (net (code "83") (name "/SCL") (class "Default")
      (node (ref "P22") (pin "26") (pinfunction "Pin_26_26") (pintype "passive"))
      (node (ref "U23") (pin "K13") (pinfunction "I2C0_SCL_K13") (pintype "passive"))
    )
    (net (code "84") (name "/SCT_CLK") (class "Default")
      (node (ref "U23") (pin "M14") (pinfunction "P6_4_M14") (pintype "passive"))
    )
    (net (code "85") (name "/SDA") (class "Default")
      (node (ref "P22") (pin "24") (pinfunction "Pin_24_24") (pintype "passive"))
      (node (ref "U23") (pin "K14") (pinfunction "I2C0_SDA_K14") (pintype "passive"))
    )
    (net (code "86") (name "/SD_CD") (class "Default")
      (node (ref "P28") (pin "3") (pinfunction "Pin_3_3") (pintype "passive"))
      (node (ref "U23") (pin "L8") (pinfunction "P1_13_L8") (pintype "passive"))
    )
    (net (code "87") (name "/SD_CLK") (class "Default")
      (node (ref "P28") (pin "11") (pinfunction "Pin_11_11") (pintype "passive"))
      (node (ref "U23") (pin "M4") (pinfunction "CLK0_M4") (pintype "passive"))
    )
    (net (code "88") (name "/SD_CMD") (class "Default")
      (node (ref "P28") (pin "9") (pinfunction "Pin_9_9") (pintype "passive"))
      (node (ref "U23") (pin "P3") (pinfunction "P1_6_P3") (pintype "passive"))
    )
    (net (code "89") (name "/SD_DAT0") (class "Default")
      (node (ref "P28") (pin "7") (pinfunction "Pin_7_7") (pintype "passive"))
      (node (ref "U23") (pin "N5") (pinfunction "P1_9_N5") (pintype "passive"))
    )
    (net (code "90") (name "/SD_DAT1") (class "Default")
      (node (ref "P28") (pin "6") (pinfunction "Pin_6_6") (pintype "passive"))
      (node (ref "U23") (pin "N6") (pinfunction "P1_10_N6") (pintype "passive"))
    )
    (net (code "91") (name "/SD_DAT2") (class "Default")
      (node (ref "P28") (pin "5") (pinfunction "Pin_5_5") (pintype "passive"))
      (node (ref "U23") (pin "P8") (pinfunction "P1_11_P8") (pintype "passive"))
    )
    (net (code "92") (name "/SD_DAT3") (class "Default")
      (node (ref "P28") (pin "4") (pinfunction "Pin_4_4") (pintype "passive"))
      (node (ref "U23") (pin "P7") (pinfunction "P1_12_P7") (pintype "passive"))
    )
    (net (code "93") (name "/SD_POW") (class "Default")
      (node (ref "P28") (pin "10") (pinfunction "Pin_10_10") (pintype "passive"))
      (node (ref "U23") (pin "N3") (pinfunction "P1_5_N3") (pintype "passive"))
    )
    (net (code "94") (name "/SD_VOLT0") (class "Default")
      (node (ref "P28") (pin "8") (pinfunction "Pin_8_8") (pintype "passive"))
      (node (ref "U23") (pin "M5") (pinfunction "P1_8_M5") (pintype "passive"))
    )
    (net (code "95") (name "/SGPIO0") (class "Default")
      (node (ref "U23") (pin "K3") (pinfunction "P0_0_K3") (pintype "passive"))
    )
    (net (code "96") (name "/SGPIO1") (class "Default")
      (node (ref "U23") (pin "K2") (pinfunction "P0_1_K2") (pintype "passive"))
    )
    (net (code "97") (name "/SGPIO2") (class "Default")
      (node (ref "U23") (pin "P11") (pinfunction "P1_15_P11") (pintype "passive"))
    )
    (net (code "98") (name "/SGPIO3") (class "Default")
      (node (ref "U23") (pin "L5") (pinfunction "P1_16_L5") (pintype "passive"))
    )
    (net (code "99") (name "/SGPIO4") (class "Default")
      (node (ref "U23") (pin "M8") (pinfunction "P9_4_M8") (pintype "passive"))
    )
    (net (code "100") (name "/SGPIO5") (class "Default")
      (node (ref "U23") (pin "K12") (pinfunction "P6_6_K12") (pintype "passive"))
    )
    (net (code "101") (name "/SGPIO6") (class "Default")
      (node (ref "U23") (pin "L13") (pinfunction "P2_2_L13") (pintype "passive"))
    )
    (net (code "102") (name "/SGPIO7") (class "Default")
      (node (ref "U23") (pin "L1") (pinfunction "P1_0_L1") (pintype "passive"))
    )
    (net (code "103") (name "/SGPIO8") (class "Default")
      (node (ref "U23") (pin "E4") (pinfunction "P8_0_E4") (pintype "passive"))
    )
    (net (code "104") (name "/SGPIO9") (class "Default")
      (node (ref "U23") (pin "P5") (pinfunction "P9_3_P5") (pintype "passive"))
    )
    (net (code "105") (name "/SGPIO10") (class "Default")
      (node (ref "U23") (pin "J4") (pinfunction "P8_2_J4") (pintype "passive"))
    )
    (net (code "106") (name "/SGPIO11") (class "Default")
      (node (ref "U23") (pin "L6") (pinfunction "P1_17_L6") (pintype "passive"))
    )
    (net (code "107") (name "/SGPIO12") (class "Default")
      (node (ref "U23") (pin "N10") (pinfunction "P1_18_N10") (pintype "passive"))
    )
    (net (code "108") (name "/SPIFI_CIPO") (class "Default")
      (node (ref "U20") (pin "2") (pinfunction "DO/IO_{1}_2") (pintype "passive"))
      (node (ref "U23") (pin "B12") (pinfunction "P3_6_B12") (pintype "passive"))
    )
    (net (code "109") (name "/SPIFI_COPI") (class "Default")
      (node (ref "U20") (pin "5") (pinfunction "DI/IO_{0}_5") (pintype "passive"))
      (node (ref "U23") (pin "C10") (pinfunction "P3_7_C10") (pintype "passive"))
    )
    (net (code "110") (name "/SPIFI_SCK") (class "Default")
      (node (ref "U20") (pin "6") (pinfunction "CLK_6") (pintype "passive"))
      (node (ref "U23") (pin "B13") (pinfunction "P3_3_B13") (pintype "passive"))
    )
    (net (code "111") (name "/SPIFI_SIO2") (class "Default")
      (node (ref "U20") (pin "3") (pinfunction "~{{WP}/IO_{2}}_3") (pintype "passive"))
      (node (ref "U23") (pin "C11") (pinfunction "P3_5_C11") (pintype "passive"))
    )
    (net (code "112") (name "/SPIFI_SIO3") (class "Default")
      (node (ref "U20") (pin "7") (pinfunction "~{{HOLD}/}{RESET}/IO_{3}_7") (pintype "passive"))
      (node (ref "U23") (pin "C14") (pinfunction "P3_4_C14") (pintype "passive"))
    )
    (net (code "113") (name "/SPIFI_~{{CS}}") (class "Default")
      (node (ref "TP64") (pin "1") (pinfunction "1_1") (pintype "passive"))
      (node (ref "U20") (pin "1") (pinfunction "~{{CS}}_1") (pintype "passive"))
      (node (ref "U23") (pin "C9") (pinfunction "P3_8_C9") (pintype "passive"))
    )
    (net (code "114") (name "/SSP1_CIPO") (class "Default")
      (node (ref "U23") (pin "M2") (pinfunction "P1_3_M2") (pintype "passive"))
    )
    (net (code "115") (name "/SSP1_COPI") (class "Default")
      (node (ref "R140") (pin "2") (pinfunction "2_2") (pintype "passive"))
    )
    (net (code "116") (name "/SSP1_SCK") (class "Default")
      (node (ref "R141") (pin "2") (pinfunction "2_2") (pintype "passive"))
    )
    (net (code "117") (name "/TCK") (class "Default")
      (node (ref "P26") (pin "4") (pinfunction "Pin_4_4") (pintype "passive"))
      (node (ref "R66") (pin "2") (pinfunction "2_2") (pintype "passive"))
      (node (ref "TP25") (pin "1") (pinfunction "1_1") (pintype "passive"))
      (node (ref "U23") (pin "G5") (pinfunction "TCK/SWDCLK_G5") (pintype "passive"))
    )
    (net (code "118") (name "/TDI") (class "Default")
      (node (ref "P26") (pin "8") (pinfunction "Pin_8_8") (pintype "passive"))
      (node (ref "TP28") (pin "1") (pinfunction "1_1") (pintype "passive"))
      (node (ref "U23") (pin "H4") (pinfunction "TDI_H4") (pintype "passive"))
    )
    (net (code "119") (name "/TDO") (class "Default")
      (node (ref "P26") (pin "6") (pinfunction "Pin_6_6") (pintype "passive"))
      (node (ref "R63") (pin "1") (pinfunction "1_1") (pintype "passive"))
      (node (ref "TP27") (pin "1") (pinfunction "1_1") (pintype "passive"))
      (node (ref "U23") (pin "J5") (pinfunction "TDO/SWO_J5") (pintype "passive"))
    )
    (net (code "120") (name "/TMS") (class "Default")
      (node (ref "P26") (pin "2") (pinfunction "Pin_2_2") (pintype "passive"))
      (node (ref "TP26") (pin "1") (pinfunction "1_1") (pintype "passive"))
      (node (ref "U23") (pin "K5") (pinfunction "TMS/SWDIO_K5") (pintype "passive"))
    )
    (net (code "121") (name "/TRIGGER.IN") (class "Default")
      (node (ref "P28") (pin "16") (pinfunction "Pin_16_16") (pintype "passive"))
      (node (ref "R127") (pin "1") (pinfunction "1_1") (pintype "passive"))
    )
    (net (code "122") (name "/TRIGGER.OUT") (class "Default")
      (node (ref "P28") (pin "15") (pinfunction "Pin_15_15") (pintype "passive"))
      (node (ref "R6") (pin "2") (pinfunction "2_2") (pintype "passive"))
    )
    (net (code "123") (name "/TX_EN") (class "Default")
      (node (ref "U23") (pin "L14") (pinfunction "P6_5_L14") (pintype "passive"))
    )
    (net (code "124") (name "/U0_RXD") (class "Default")
      (node (ref "P22") (pin "19") (pinfunction "Pin_19_19") (pintype "passive"))
      (node (ref "U23") (pin "M13") (pinfunction "P2_1_M13") (pintype "passive"))
    )
    (net (code "125") (name "/U0_TXD") (class "Default")
      (node (ref "P22") (pin "20") (pinfunction "Pin_20_20") (pintype "passive"))
      (node (ref "U23") (pin "N14") (pinfunction "P2_0_N14") (pintype "passive"))
    )
    (net (code "126") (name "/USB0_VBUS") (class "Default")
      (node (ref "R62") (pin "1") (pinfunction "1_1") (pintype "passive"))
      (node (ref "R65") (pin "2") (pinfunction "2_2") (pintype "passive"))
      (node (ref "U23") (pin "E1") (pinfunction "USB0_VBUS_E1") (pintype "passive"))
    )
    (net (code "127") (name "/USB_DATA.D+") (class "Default")
      (node (ref "U23") (pin "E2") (pinfunction "USB0_DP_E2") (pintype "passive"))
    )
    (net (code "128") (name "/USB_DATA.D-") (class "Default")
      (node (ref "U23") (pin "F2") (pinfunction "USB0_DM_F2") (pintype "passive"))
    )
    (net (code "129") (name "/VBAT") (class "Default")
      (node (ref "C136") (pin "1") (pinfunction "1_1") (pintype "passive"))
      (node (ref "P20") (pin "1") (pinfunction "Pin_1_1") (pintype "passive"))
      (node (ref "U23") (pin "B9") (pinfunction "VBAT_B9") (pintype "passive"))
    )
    (net (code "130") (name "/VBUS") (class "Default")
      (node (ref "P20") (pin "21") (pinfunction "Pin_21_21") (pintype "passive"))
    )
    (net (code "131") (name "/VBUSCTRL") (class "Default")
      (node (ref "P20") (pin "17") (pinfunction "Pin_17_17") (pintype "passive"))
      (node (ref "R37") (pin "2") (pinfunction "2_2") (pintype "passive"))
    )
    (net (code "132") (name "/VBUS_SAFE") (class "Default")
      (node (ref "R62") (pin "2") (pinfunction "2_2") (pintype "passive"))
    )
    (net (code "133") (name "/VIN") (class "Default")
      (node (ref "P20") (pin "22") (pinfunction "Pin_22_22") (pintype "passive"))
    )
    (net (code "134") (name "/WAKEUP") (class "Default")
      (node (ref "P20") (pin "4") (pinfunction "Pin_4_4") (pintype "passive"))
      (node (ref "R48") (pin "2") (pinfunction "2_2") (pintype "passive"))
      (node (ref "U23") (pin "A9") (pinfunction "WAKEUP0_A9") (pintype "passive"))
    )
    (net (code "135") (name "/XCVR.LD") (class "Default")
      (node (ref "U23") (pin "M9") (pinfunction "P9_6_M9") (pintype "passive"))
    )
    (net (code "136") (name "/XCVR.RSSI") (class "Default")
      (node (ref "U23") (pin "C4") (pinfunction "ADC0_1/ADC1_1_C4") (pintype "passive"))
    )
    (net (code "137") (name "/XCVR.RXHP") (class "Default")
      (node (ref "U23") (pin "P13") (pinfunction "PD_15_P13") (pintype "passive"))
    )
    (net (code "138") (name "/XCVR.RXTX") (class "Default")
      (node (ref "U23") (pin "L12") (pinfunction "PE_2_L12") (pintype "passive"))
    )
    (net (code "139") (name "/XCVR.~{{CS}}") (class "Default")
      (node (ref "U23") (pin "L11") (pinfunction "PD_14_L11") (pintype "passive"))
    )
    (net (code "140") (name "/XCVR.~{{SHDN}}") (class "Default")
      (node (ref "U23") (pin "M12") (pinfunction "PE_1_M12") (pintype "passive"))
    )
    (net (code "141") (name "/XTAL1") (class "Default")
      (node (ref "C157") (pin "1") (pinfunction "1_1") (pintype "passive"))
      (node (ref "U23") (pin "C1") (pinfunction "XTAL1_C1") (pintype "passive"))
      (node (ref "X2") (pin "1") (pinfunction "1_1") (pintype "passive"))
    )
    (net (code "142") (name "/XTAL2") (class "Default")
      (node (ref "C158") (pin "1") (pinfunction "1_1") (pintype "passive"))
      (node (ref "U23") (pin "D1") (pinfunction "XTAL2_D1") (pintype "passive"))
      (node (ref "X2") (pin "3") (pinfunction "3_3") (pintype "passive"))
    )
    (net (code "153") (name "/~{{3V3AUX_EN}}") (class "Default")
      (node (ref "U23") (pin "H11") (pinfunction "P6_7_H11") (pintype "passive"))
    )
    (net (code "154") (name "/~{{3V3AUX_OC}}") (class "Default")
      (node (ref "U23") (pin "F11") (pinfunction "P6_11_F11") (pintype "passive"))
    )
    (net (code "155") (name "/~{{BIAS_EN}}") (class "Default")
      (node (ref "U23") (pin "D13") (pinfunction "P2_12_D13") (pintype "passive"))
    )
    (net (code "156") (name "/~{{BIAS_OC}}") (class "Default")
      (node (ref "U23") (pin "E13") (pinfunction "P2_11_E13") (pintype "passive"))
    )
    (net (code "157") (name "/~{{LED1}}") (class "Default")
      (node (ref "D4") (pin "2") (pinfunction "K1_2") (pintype "passive"))
      (node (ref "D4") (pin "4") (pinfunction "K2_4") (pintype "passive"))
      (node (ref "U23") (pin "D3") (pinfunction "P4_1_D3") (pintype "passive"))
    )
    (net (code "158") (name "/~{{LED2}}") (class "Default")
      (node (ref "D5") (pin "1") (pinfunction "K_1") (pintype "passive"))
      (node (ref "U23") (pin "A2") (pinfunction "P4_2_A2") (pintype "passive"))
    )
    (net (code "159") (name "/~{{LED3}}") (class "Default")
      (node (ref "D6") (pin "4") (pinfunction "K2_4") (pintype "passive"))
      (node (ref "U23") (pin "F13") (pinfunction "P6_12_F13") (pintype "passive"))
    )
    (net (code "160") (name "/~{{LED4}}") (class "Default")
      (node (ref "D7") (pin "2") (pinfunction "K1_2") (pintype "passive"))
      (node (ref "D7") (pin "4") (pinfunction "K2_4") (pintype "passive"))
      (node (ref "U23") (pin "J3") (pinfunction "P8_6_J3") (pintype "passive"))
    )
    (net (code "161") (name "/~{{MIX_EN}}") (class "Default")
      (node (ref "U23") (pin "N13") (pinfunction "P6_3_N13") (pintype "passive"))
    )
    (net (code "162") (name "/~{{RESET}}") (class "Default")
      (node (ref "P22") (pin "3") (pinfunction "Pin_3_3") (pintype "passive"))
      (node (ref "P26") (pin "10") (pinfunction "Pin_10_10") (pintype "passive"))
      (node (ref "R19") (pin "1") (pinfunction "1_1") (pintype "passive"))
      (node (ref "U23") (pin "C7") (pinfunction "~{{RESET}}_C7") (pintype "passive"))
    )
    (net (code "163") (name "/~{{TRST}}") (class "Default")
      (node (ref "TP5") (pin "1") (pinfunction "1_1") (pintype "passive"))
      (node (ref "U23") (pin "L4") (pinfunction "~{{TRST}}_L4") (pintype "passive"))
    )
    (net (code "164") (name "/~{{VBUS_IN_EN}}") (class "Default")
      (node (ref "U23") (pin "H2") (pinfunction "P8_4_H2") (pintype "passive"))
    )
    (net (code "165") (name "/~{{VIN_IN_EN}}") (class "Default")
      (node (ref "U23") (pin "H1") (pinfunction "P8_5_H1") (pintype "passive"))
    )
    (net (code "166") (name "3V3AUX") (class "Default")
      (node (ref "P20") (pin "3") (pinfunction "Pin_3_3") (pintype "passive"))
      (node (ref "P22") (pin "11") (pinfunction "Pin_11_11") (pintype "passive"))
      (node (ref "P28") (pin "1") (pinfunction "Pin_1_1") (pintype "passive"))
    )
    (net (code "167") (name "3V3FPGA") (class "Default")
      (node (ref "C140") (pin "1") (pinfunction "1_1") (pintype "passive"))
      (node (ref "R76") (pin "2") (pinfunction "2_2") (pintype "passive"))
    )
    (net (code "168") (name "3V3LED") (class "Default")
      (node (ref "C110") (pin "1") (pinfunction "1_1") (pintype "passive"))
      (node (ref "C124") (pin "1") (pinfunction "1_1") (pintype "passive"))
      (node (ref "C80") (pin "1") (pinfunction "1_1") (pintype "passive"))
      (node (ref "C81") (pin "1") (pinfunction "1_1") (pintype "passive"))
      (node (ref "R125") (pin "2") (pinfunction "2_2") (pintype "passive"))
      (node (ref "R49") (pin "1") (pinfunction "1_1") (pintype "passive"))
      (node (ref "R50") (pin "2") (pinfunction "2_2") (pintype "passive"))
      (node (ref "R72") (pin "2") (pinfunction "2_2") (pintype "passive"))
      (node (ref "R73") (pin "2") (pinfunction "2_2") (pintype "passive"))
      (node (ref "R74") (pin "2") (pinfunction "2_2") (pintype "passive"))
      (node (ref "R75") (pin "2") (pinfunction "2_2") (pintype "passive"))
      (node (ref "SW1") (pin "2") (pinfunction "2_2") (pintype "passive"))
    )
    (net (code "169") (name "GND") (class "Default")
      (node (ref "C110") (pin "2") (pinfunction "2_2") (pintype "passive"))
      (node (ref "C118") (pin "2") (pinfunction "2_2") (pintype "passive"))
      (node (ref "C124") (pin "2") (pinfunction "2_2") (pintype "passive"))
      (node (ref "C128") (pin "2") (pinfunction "2_2") (pintype "passive"))
      (node (ref "C129") (pin "2") (pinfunction "2_2") (pintype "passive"))
      (node (ref "C130") (pin "2") (pinfunction "2_2") (pintype "passive"))
      (node (ref "C131") (pin "2") (pinfunction "2_2") (pintype "passive"))
      (node (ref "C132") (pin "2") (pinfunction "2_2") (pintype "passive"))
      (node (ref "C133") (pin "2") (pinfunction "2_2") (pintype "passive"))
      (node (ref "C134") (pin "2") (pinfunction "2_2") (pintype "passive"))
      (node (ref "C135") (pin "2") (pinfunction "2_2") (pintype "passive"))
      (node (ref "C136") (pin "2") (pinfunction "2_2") (pintype "passive"))
      (node (ref "C137") (pin "2") (pinfunction "2_2") (pintype "passive"))
      (node (ref "C138") (pin "2") (pinfunction "2_2") (pintype "passive"))
      (node (ref "C140") (pin "2") (pinfunction "2_2") (pintype "passive"))
      (node (ref "C144") (pin "2") (pinfunction "2_2") (pintype "passive"))
      (node (ref "C157") (pin "2") (pinfunction "2_2") (pintype "passive"))
      (node (ref "C158") (pin "2") (pinfunction "2_2") (pintype "passive"))
      (node (ref "C162") (pin "2") (pinfunction "2_2") (pintype "passive"))
      (node (ref "C164") (pin "2") (pinfunction "2_2") (pintype "passive"))
      (node (ref "C80") (pin "2") (pinfunction "2_2") (pintype "passive"))
      (node (ref "C81") (pin "2") (pinfunction "2_2") (pintype "passive"))
      (node (ref "D2") (pin "1") (pinfunction "K_1") (pintype "passive"))
      (node (ref "D8") (pin "2") (pinfunction "K1_2") (pintype "passive"))
      (node (ref "P20") (pin "13") (pinfunction "Pin_13_13") (pintype "passive"))
      (node (ref "P20") (pin "15") (pinfunction "Pin_15_15") (pintype "passive"))
      (node (ref "P20") (pin "19") (pinfunction "Pin_19_19") (pintype "passive"))
      (node (ref "P22") (pin "10") (pinfunction "Pin_10_10") (pintype "passive"))
      (node (ref "P22") (pin "18") (pinfunction "Pin_18_18") (pintype "passive"))
      (node (ref "P22") (pin "4") (pinfunction "Pin_4_4") (pintype "passive"))
      (node (ref "P26") (pin "3") (pinfunction "Pin_3_3") (pintype "passive"))
      (node (ref "P26") (pin "5") (pinfunction "Pin_5_5") (pintype "passive"))
      (node (ref "P26") (pin "9") (pinfunction "Pin_9_9") (pintype "passive"))
      (node (ref "P28") (pin "12") (pinfunction "Pin_12_12") (pintype "passive"))
      (node (ref "P28") (pin "2") (pinfunction "Pin_2_2") (pintype "passive"))
      (node (ref "R107") (pin "2") (pinfunction "2_2") (pintype "passive"))
      (node (ref "R39") (pin "2") (pinfunction "2_2") (pintype "passive"))
      (node (ref "R65") (pin "1") (pinfunction "1_1") (pintype "passive"))
      (node (ref "R68") (pin "2") (pinfunction "2_2") (pintype "passive"))
      (node (ref "R69") (pin "2") (pinfunction "2_2") (pintype "passive"))
      (node (ref "R7") (pin "2") (pinfunction "2_2") (pintype "passive"))
      (node (ref "R82") (pin "1") (pinfunction "1_1") (pintype "passive"))
      (node (ref "R93") (pin "2") (pinfunction "2_2") (pintype "passive"))
      (node (ref "SW1") (pin "SH") (pinfunction "B_SH") (pintype "passive"))
      (node (ref "SW2") (pin "2") (pinfunction "2_2") (pintype "passive"))
      (node (ref "SW2") (pin "SH") (pinfunction "B_SH") (pintype "passive"))
      (node (ref "U20") (pin "4") (pinfunction "GND_4") (pintype "passive"))
      (node (ref "U23") (pin "A3") (pinfunction "VSSA_A3") (pintype "passive"))
      (node (ref "U23") (pin "D7") (pinfunction "VSS_D7") (pintype "passive"))
      (node (ref "U23") (pin "E6") (pinfunction "VSS_E6") (pintype "passive"))
      (node (ref "U23") (pin "E7") (pinfunction "VSS_E7") (pintype "passive"))
      (node (ref "U23") (pin "E9") (pinfunction "VSS_E9") (pintype "passive"))
      (node (ref "U23") (pin "F1") (pinfunction "USB0_VSSA_REF_F1") (pintype "passive"))
      (node (ref "U23") (pin "F10") (pinfunction "VSS_F10") (pintype "passive"))
      (node (ref "U23") (pin "G3") (pinfunction "USB0_VSSA_TERM_G3") (pintype "passive"))
      (node (ref "U23") (pin "K6") (pinfunction "VSS_K6") (pintype "passive"))
      (node (ref "U23") (pin "K9") (pinfunction "VSS_K9") (pintype "passive"))
      (node (ref "X2") (pin "2") (pinfunction "2_2") (pintype "passive"))
      (node (ref "X2") (pin "4") (pinfunction "4_4") (pintype "passive"))
    )
    (net (code "170") (name "Net-(D2-A)") (class "Default")
      (node (ref "D2") (pin "2") (pinfunction "A_2") (pintype "passive"))
      (node (ref "R18") (pin "1") (pinfunction "1_1") (pintype "passive"))
      (node (ref "TP10") (pin "1") (pinfunction "1_1") (pintype "passive"))
    )
    (net (code "171") (name "Net-(D4-A1)") (class "Default")
      (node (ref "D4") (pin "1") (pinfunction "A1_1") (pintype "passive"))
      (node (ref "R72") (pin "1") (pinfunction "1_1") (pintype "passive"))
      (node (ref "TP12") (pin "1") (pinfunction "1_1") (pintype "passive"))
    )
    (net (code "172") (name "Net-(D4-A2)") (class "Default")
      (node (ref "D4") (pin "3") (pinfunction "A2_3") (pintype "passive"))
      (node (ref "R125") (pin "1") (pinfunction "1_1") (pintype "passive"))
      (node (ref "TP11") (pin "1") (pinfunction "1_1") (pintype "passive"))
    )
    (net (code "173") (name "Net-(D5-A)") (class "Default")
      (node (ref "D5") (pin "2") (pinfunction "A_2") (pintype "passive"))
      (node (ref "R73") (pin "1") (pinfunction "1_1") (pintype "passive"))
      (node (ref "TP13") (pin "1") (pinfunction "1_1") (pintype "passive"))
    )
    (net (code "174") (name "Net-(D6-A2)") (class "Default")
      (node (ref "D6") (pin "3") (pinfunction "A2_3") (pintype "passive"))
      (node (ref "R74") (pin "1") (pinfunction "1_1") (pintype "passive"))
      (node (ref "TP14") (pin "1") (pinfunction "1_1") (pintype "passive"))
    )
    (net (code "175") (name "Net-(D7-A1)") (class "Default")
      (node (ref "D7") (pin "1") (pinfunction "A1_1") (pintype "passive"))
      (node (ref "R75") (pin "1") (pinfunction "1_1") (pintype "passive"))
      (node (ref "TP8") (pin "1") (pinfunction "1_1") (pintype "passive"))
    )
    (net (code "176") (name "Net-(D7-A2)") (class "Default")
      (node (ref "D7") (pin "3") (pinfunction "A2_3") (pintype "passive"))
      (node (ref "R50") (pin "1") (pinfunction "1_1") (pintype "passive"))
      (node (ref "TP7") (pin "1") (pinfunction "1_1") (pintype "passive"))
    )
    (net (code "177") (name "Net-(D8-A1)") (class "Default")
      (node (ref "D8") (pin "1") (pinfunction "A1_1") (pintype "passive"))
      (node (ref "R76") (pin "1") (pinfunction "1_1") (pintype "passive"))
      (node (ref "TP9") (pin "1") (pinfunction "1_1") (pintype "passive"))
    )
    (net (code "178") (name "Net-(R19-Pad2)") (class "Default")
      (node (ref "R19") (pin "2") (pinfunction "2_2") (pintype "passive"))
      (node (ref "R49") (pin "2") (pinfunction "2_2") (pintype "passive"))
      (node (ref "SW2") (pin "1") (pinfunction "1_1") (pintype "passive"))
      (node (ref "TP30") (pin "1") (pinfunction "1_1") (pintype "passive"))
    )
    (net (code "179") (name "Net-(R30-Pad2)") (class "Default")
      (node (ref "R30") (pin "2") (pinfunction "2_2") (pintype "passive"))
      (node (ref "R7") (pin "1") (pinfunction "1_1") (pintype "passive"))
      (node (ref "SW1") (pin "1") (pinfunction "1_1") (pintype "passive"))
      (node (ref "TP31") (pin "1") (pinfunction "1_1") (pintype "passive"))
    )
    (net (code "180") (name "Net-(U23-P1_4)") (class "Default")
      (node (ref "R140") (pin "1") (pinfunction "1_1") (pintype "passive"))
      (node (ref "U23") (pin "P2") (pinfunction "P1_4_P2") (pintype "passive"))
    )
    (net (code "181") (name "Net-(U23-P1_19)") (class "Default")
      (node (ref "R141") (pin "1") (pinfunction "1_1") (pintype "passive"))
      (node (ref "U23") (pin "N9") (pinfunction "P1_19_N9") (pintype "passive"))
    )
    (net (code "182") (name "Net-(U23-P2_6)") (class "Default")
      (node (ref "R6") (pin "1") (pinfunction "1_1") (pintype "passive"))
      (node (ref "U23") (pin "J14") (pinfunction "P2_6_J14") (pintype "passive"))
    )
    (net (code "183") (name "Net-(U23-P4_3)") (class "Default")
      (node (ref "R37") (pin "1") (pinfunction "1_1") (pintype "passive"))
      (node (ref "R82") (pin "2") (pinfunction "2_2") (pintype "passive"))
      (node (ref "U23") (pin "B2") (pinfunction "P4_3_B2") (pintype "passive"))
    )
    (net (code "184") (name "Net-(U23-P4_6)") (class "Default")
      (node (ref "R107") (pin "1") (pinfunction "1_1") (pintype "passive"))
      (node (ref "U23") (pin "B1") (pinfunction "P4_6_B1") (pintype "passive"))
    )
    (net (code "185") (name "Net-(U23-PD_12)") (class "Default")
      (node (ref "R127") (pin "2") (pinfunction "2_2") (pintype "passive"))
      (node (ref "U23") (pin "P9") (pinfunction "PD_12_P9") (pintype "passive"))
    )
    (net (code "186") (name "VAA") (class "Default")
      (node (ref "C162") (pin "1") (pinfunction "1_1") (pintype "passive"))
      (node (ref "R18") (pin "2") (pinfunction "2_2") (pintype "passive"))
    )
    (net (code "187") (name "VCC") (class "Default")
      (node (ref "C128") (pin "1") (pinfunction "1_1") (pintype "passive"))
      (node (ref "C129") (pin "1") (pinfunction "1_1") (pintype "passive"))
      (node (ref "C130") (pin "1") (pinfunction "1_1") (pintype "passive"))
      (node (ref "C131") (pin "1") (pinfunction "1_1") (pintype "passive"))
      (node (ref "C132") (pin "1") (pinfunction "1_1") (pintype "passive"))
      (node (ref "C133") (pin "1") (pinfunction "1_1") (pintype "passive"))
      (node (ref "C134") (pin "1") (pinfunction "1_1") (pintype "passive"))
      (node (ref "C135") (pin "1") (pinfunction "1_1") (pintype "passive"))
      (node (ref "C137") (pin "1") (pinfunction "1_1") (pintype "passive"))
      (node (ref "C138") (pin "1") (pinfunction "1_1") (pintype "passive"))
      (node (ref "C144") (pin "1") (pinfunction "1_1") (pintype "passive"))
      (node (ref "P26") (pin "1") (pinfunction "Pin_1_1") (pintype "passive"))
      (node (ref "R38") (pin "1") (pinfunction "1_1") (pintype "passive"))
      (node (ref "R48") (pin "1") (pinfunction "1_1") (pintype "passive"))
      (node (ref "R59") (pin "1") (pinfunction "1_1") (pintype "passive"))
      (node (ref "R63") (pin "2") (pinfunction "2_2") (pintype "passive"))
      (node (ref "R64") (pin "2") (pinfunction "2_2") (pintype "passive"))
      (node (ref "R66") (pin "1") (pinfunction "1_1") (pintype "passive"))
      (node (ref "R67") (pin "2") (pinfunction "2_2") (pintype "passive"))
      (node (ref "U20") (pin "8") (pinfunction "VCC_8") (pintype "passive"))
      (node (ref "U23") (pin "A6") (pinfunction "VDDA_A6") (pintype "passive"))
      (node (ref "U23") (pin "D8") (pinfunction "VDDREG_D8") (pintype "passive"))
      (node (ref "U23") (pin "E3") (pinfunction "USB0_VDDA3V3_DRIVER_E3") (pintype "passive"))
      (node (ref "U23") (pin "E8") (pinfunction "VDDREG_E8") (pintype "passive"))
      (node (ref "U23") (pin "F3") (pinfunction "USB0_VDDA3V3_F3") (pintype "passive"))
      (node (ref "U23") (pin "G10") (pinfunction "VDDIO_G10") (pintype "passive"))
      (node (ref "U23") (pin "H10") (pinfunction "VDDIO_H10") (pintype "passive"))
      (node (ref "U23") (pin "H5") (pinfunction "VDDIO_H5") (pintype "passive"))
      (node (ref "U23") (pin "K8") (pinfunction "VDDIO_K8") (pintype "passive"))
    )
    (net (code "188") (name "unconnected-(D6-A1-Pad1)") (class "Default")
      (node (ref "D6") (pin "1") (pinfunction "A1_1") (pintype "passive+no_connect"))
    )
    (net (code "189") (name "unconnected-(D6-K1-Pad2)") (class "Default")
      (node (ref "D6") (pin "2") (pinfunction "K1_2") (pintype "passive+no_connect"))
    )
    (net (code "190") (name "unconnected-(D8-A2-Pad3)") (class "Default")
      (node (ref "D8") (pin "3") (pinfunction "A2_3") (pintype "passive+no_connect"))
    )
    (net (code "191") (name "unconnected-(D8-K2-Pad4)") (class "Default")
      (node (ref "D8") (pin "4") (pinfunction "K2_4") (pintype "passive+no_connect"))
    )
    (net (code "192") (name "unconnected-(JP1-A-Pad1)") (class "Default")
      (node (ref "JP1") (pin "1") (pinfunction "A_1") (pintype "passive"))
    )
    (net (code "193") (name "unconnected-(JP1-B-Pad2)") (class "Default")
      (node (ref "JP1") (pin "2") (pinfunction "B_2") (pintype "passive"))
    )
    (net (code "194") (name "unconnected-(P26-Pin_7-Pad7)") (class "Default")
      (node (ref "P26") (pin "7") (pinfunction "Pin_7_7") (pintype "passive+no_connect"))
    )
    (net (code "195") (name "unconnected-(U23-NC-PadB8)") (class "Default")
      (node (ref "U23") (pin "B8") (pinfunction "NC_B8") (pintype "passive+no_connect"))
    )
    (net (code "196") (name "unconnected-(U23-P4_0-PadD4)") (class "Default")
      (node (ref "U23") (pin "D4") (pinfunction "P4_0_D4") (pintype "passive+no_connect"))
    )
    (net (code "197") (name "unconnected-(U23-P4_8-PadD2)") (class "Default")
      (node (ref "U23") (pin "D2") (pinfunction "P4_8_D2") (pintype "passive+no_connect"))
    )
    (net (code "198") (name "unconnected-(U23-P5_0-PadL2)") (class "Default")
      (node (ref "U23") (pin "L2") (pinfunction "P5_0_L2") (pintype "passive+no_connect"))
    )
    (net (code "199") (name "unconnected-(U23-P6_0-PadM10)") (class "Default")
      (node (ref "U23") (pin "M10") (pinfunction "P6_0_M10") (pintype "passive+no_connect"))
    )
    (net (code "200") (name "unconnected-(U23-P6_10-PadG13)") (class "Default")
      (node (ref "U23") (pin "G13") (pinfunction "P6_10_G13") (pintype "passive+no_connect"))
    )
    (net (code "201") (name "unconnected-(U23-P8_3-PadH3)") (class "Default")
      (node (ref "U23") (pin "H3") (pinfunction "P8_3_H3") (pintype "passive+no_connect"))
    )
    (net (code "202") (name "unconnected-(U23-P8_8-PadK1)") (class "Default")
      (node (ref "U23") (pin "K1") (pinfunction "P8_8_K1") (pintype "passive+no_connect"))
    )
    (net (code "203") (name "unconnected-(U23-PA_0-PadL10)") (class "Default")
      (node (ref "U23") (pin "L10") (pinfunction "PA_0_L10") (pintype "passive+no_connect"))
    )
    (net (code "204") (name "unconnected-(U23-PB_2-PadB11)") (class "Default")
      (node (ref "U23") (pin "B11") (pinfunction "PB_2_B11") (pintype "passive+no_connect"))
    )
    (net (code "205") (name "unconnected-(U23-PB_4-PadB10)") (class "Default")
      (node (ref "U23") (pin "B10") (pinfunction "PB_4_B10") (pintype "passive+no_connect"))
    )
    (net (code "206") (name "unconnected-(U23-RTC_ALARM-PadA10)") (class "Default")
      (node (ref "U23") (pin "A10") (pinfunction "RTC_ALARM_A10") (pintype "passive+no_connect"))
    )
    (net (code "207") (name "unconnected-(U23-USB0_ID-PadG2)") (class "Default")
      (node (ref "U23") (pin "G2") (pinfunction "USB0_ID_G2") (pintype "passive+no_connect"))
    )
    (net (code "208") (name "unconnected-(U23-USB1_DM-PadE11)") (class "Default")
      (node (ref "U23") (pin "E11") (pinfunction "USB1_DM_E11") (pintype "passive+no_connect"))
    )
    (net (code "209") (name "unconnected-(U23-USB1_DP-PadD11)") (class "Default")
      (node (ref "U23") (pin "D11") (pinfunction "USB1_DP_D11") (pintype "passive+no_connect"))
    )
    (net (code "210") (name "unconnected-(U23-WAKEUP1-PadC8)") (class "Default")
      (node (ref "U23") (pin "C8") (pinfunction "WAKEUP1_C8") (pintype "passive+no_connect"))
    )
    (net (code "211") (name "unconnected-(U23-WAKEUP2-PadE5)") (class "Default")
      (node (ref "U23") (pin "E5") (pinfunction "WAKEUP2_E5") (pintype "passive+no_connect"))
    )
  )
)
